# Urukul.net
KiCad netlist of a schematic drawn in Altium Designer
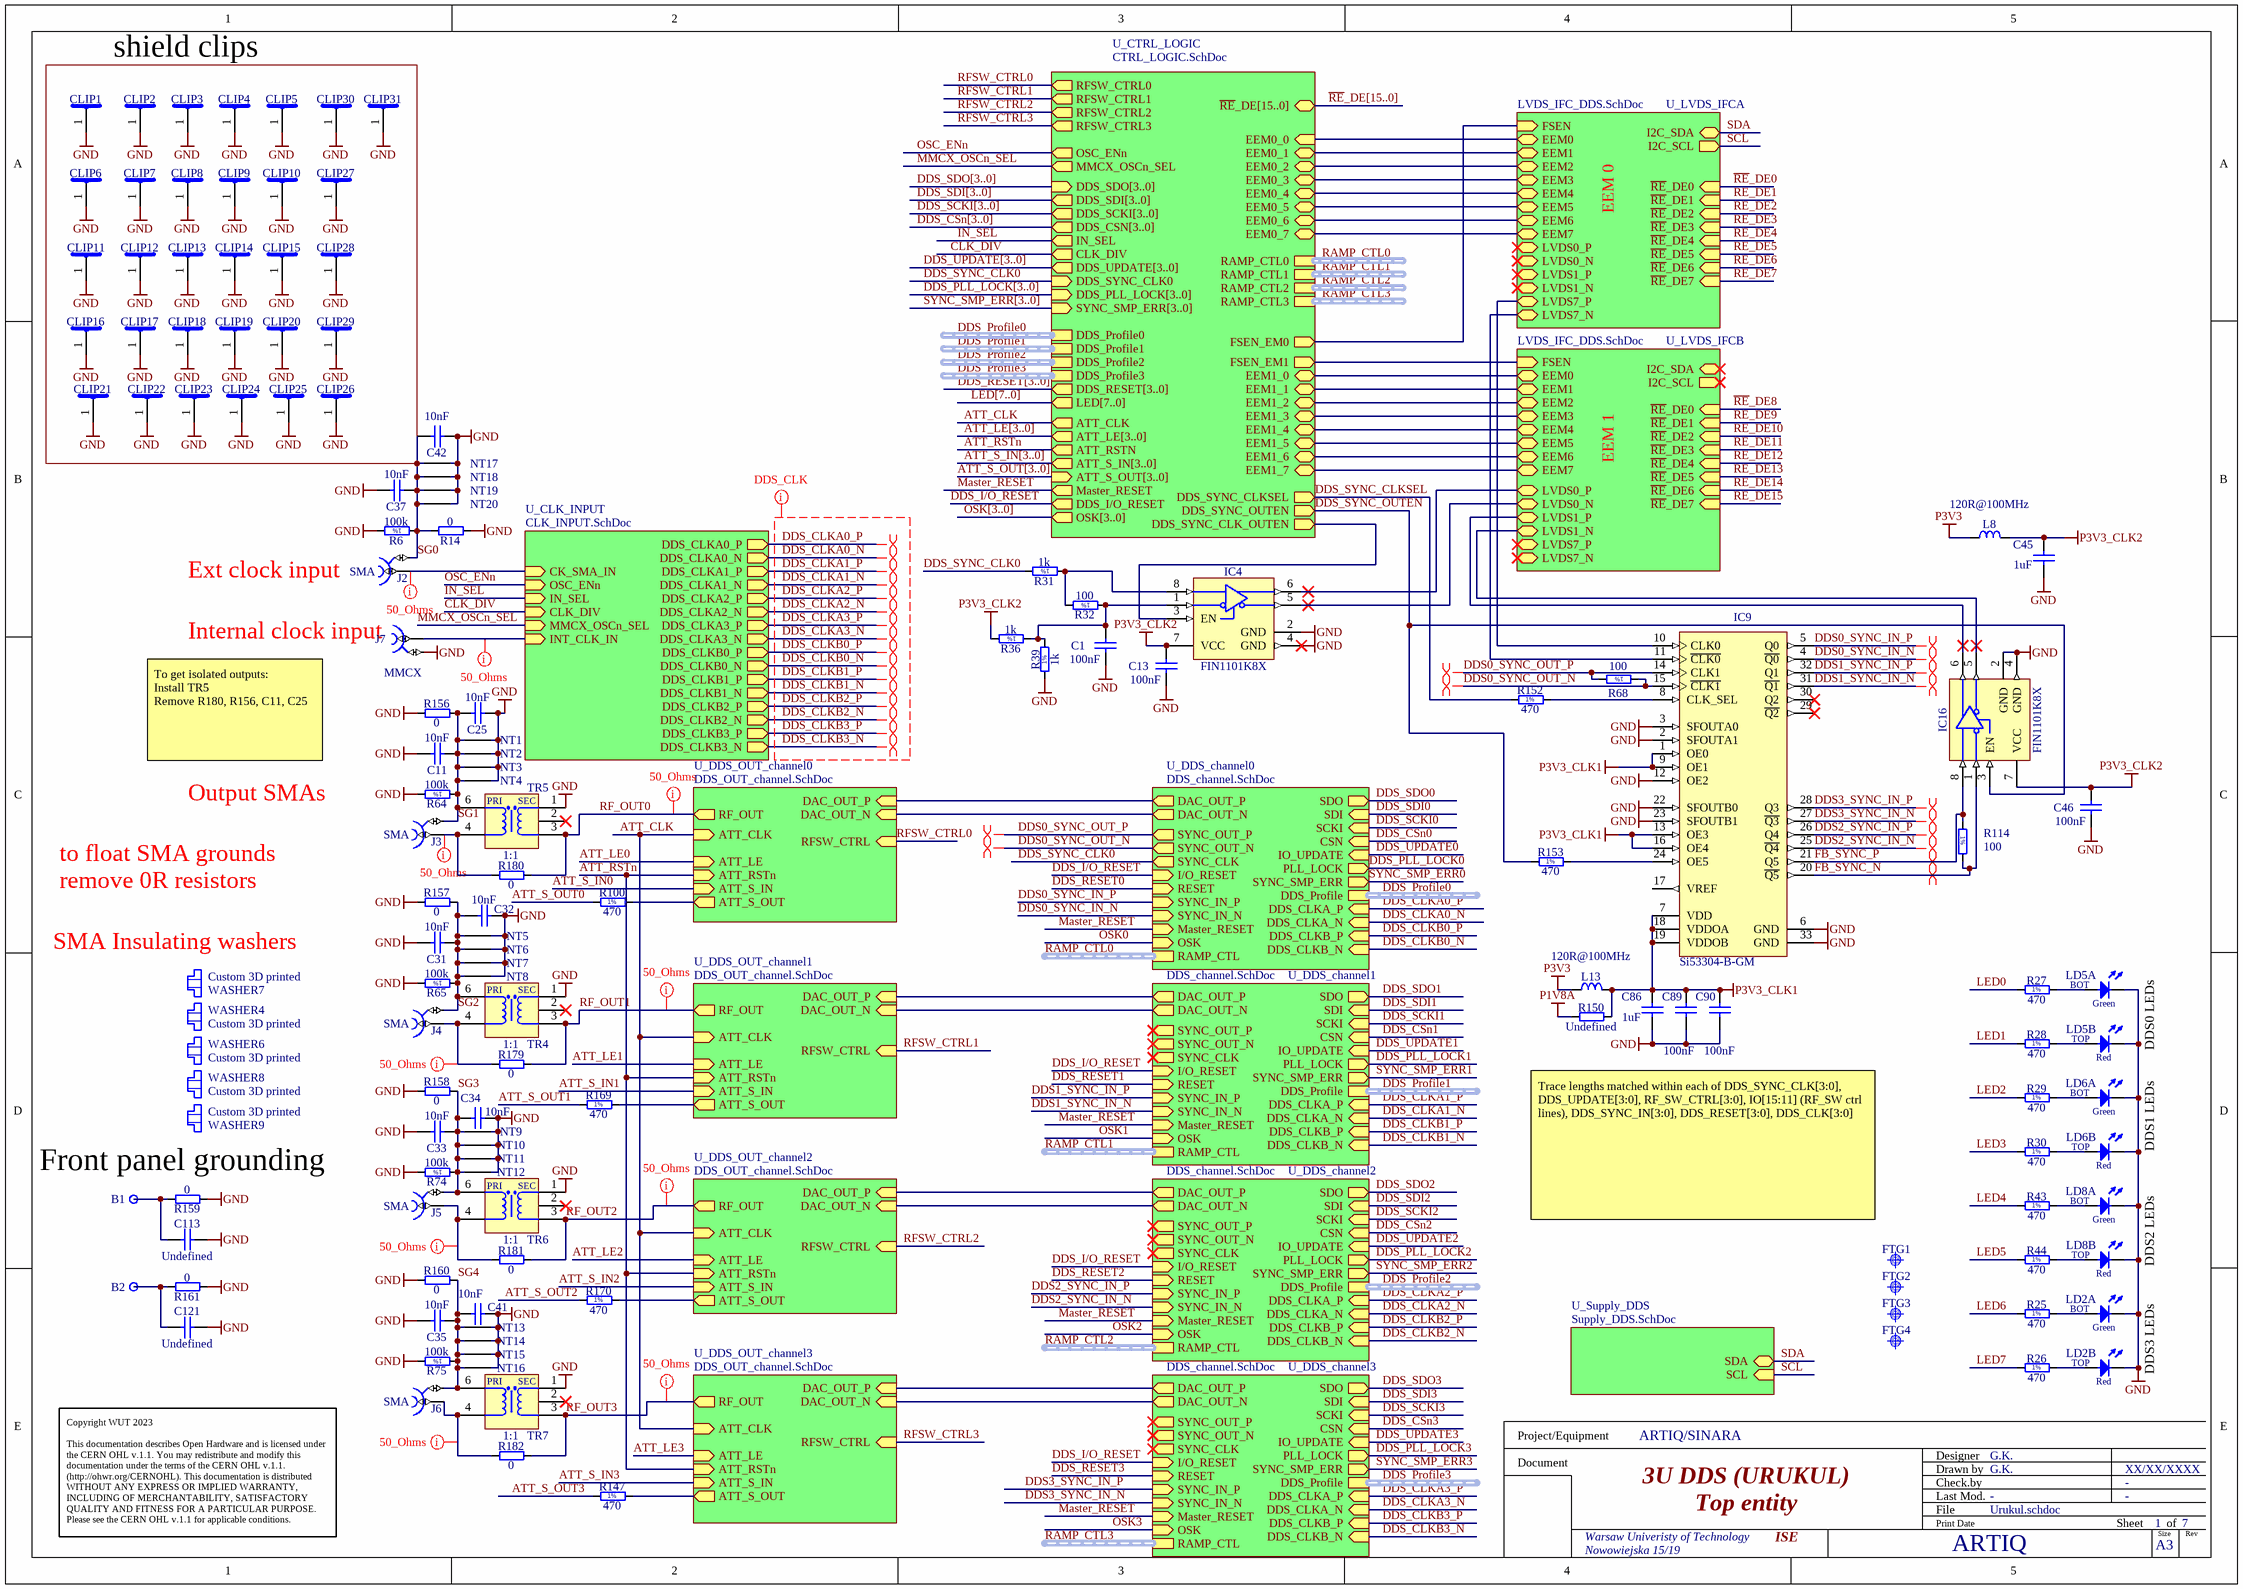
[diagram p0: Urukul.schdoc]

(export (version "E")
  (design (tool "Eeschema 10.0.6"))
  (components
    (comp (ref "B1")
      (value "Plated Hole")
      (footprint "MTG270_500")
      (description "Single Terminal Socket")
      (fields (field (name "PART NUMBER") "PLATED_HOLE2.7_PAD5.0") (field (name "AUTHOR") "CERN DEM JMW"))
      (libsource (lib "Eletro-mechanical") (part "Single Terminal Socket"))
    )
    (comp (ref "B2")
      (value "Plated Hole")
      (footprint "MTG270_500")
      (description "Single Terminal Socket")
      (fields (field (name "PART NUMBER") "PLATED_HOLE2.7_PAD5.0") (field (name "AUTHOR") "CERN DEM JMW"))
      (libsource (lib "Eletro-mechanical") (part "Single Terminal Socket"))
    )
    (comp (ref "C1")
      (value "100nF")
      (footprint "CAPC1005X55N")
      (description "Non-polarised capacitor")
      (fields
        (field (name "PART NUMBER") "CC0402_100NF_16V_10%_X5R")
        (field (name "VOLTAGE") "16V")
        (field (name "AUTHOR") "CERN DEM JLC")
      )
      (libsource (lib "Capacitors") (part "Capacitor - non polarized"))
    )
    (comp (ref "C11")
      (value "10nF")
      (footprint "CAPC1005X55N")
      (description "Non-polarised capacitor")
      (fields
        (field (name "PART NUMBER") "CC0402_10NF_16V_10%_X7R")
        (field (name "VOLTAGE") "16V")
        (field (name "AUTHOR") "CERN DEM JLC")
      )
      (libsource (lib "Capacitors") (part "Capacitor - non polarized"))
    )
    (comp (ref "C13")
      (value "100nF")
      (footprint "CAPC1005X55N")
      (description "Non-polarised capacitor")
      (fields
        (field (name "PART NUMBER") "CC0402_100NF_16V_10%_X5R")
        (field (name "VOLTAGE") "16V")
        (field (name "AUTHOR") "CERN DEM JLC")
      )
      (libsource (lib "Capacitors") (part "Capacitor - non polarized"))
    )
    (comp (ref "C25")
      (value "10nF")
      (footprint "CAPC1005X55N")
      (description "Non-polarised capacitor")
      (fields
        (field (name "PART NUMBER") "CC0402_10NF_16V_10%_X7R")
        (field (name "VOLTAGE") "16V")
        (field (name "AUTHOR") "CERN DEM JLC")
      )
      (libsource (lib "Capacitors") (part "Capacitor - non polarized"))
    )
    (comp (ref "C31")
      (value "10nF")
      (footprint "CAPC1005X55N")
      (description "Non-polarised capacitor")
      (fields
        (field (name "PART NUMBER") "CC0402_10NF_16V_10%_X7R")
        (field (name "VOLTAGE") "16V")
        (field (name "AUTHOR") "CERN DEM JLC")
      )
      (libsource (lib "Capacitors") (part "Capacitor - non polarized"))
    )
    (comp (ref "C32")
      (value "10nF")
      (footprint "CAPC1005X55N")
      (description "Non-polarised capacitor")
      (fields
        (field (name "PART NUMBER") "CC0402_10NF_16V_10%_X7R")
        (field (name "VOLTAGE") "16V")
        (field (name "AUTHOR") "CERN DEM JLC")
      )
      (libsource (lib "Capacitors") (part "Capacitor - non polarized"))
    )
    (comp (ref "C33")
      (value "10nF")
      (footprint "CAPC1005X55N")
      (description "Non-polarised capacitor")
      (fields
        (field (name "PART NUMBER") "CC0402_10NF_16V_10%_X7R")
        (field (name "VOLTAGE") "16V")
        (field (name "AUTHOR") "CERN DEM JLC")
      )
      (libsource (lib "Capacitors") (part "Capacitor - non polarized"))
    )
    (comp (ref "C34")
      (value "10nF")
      (footprint "CAPC1005X55N")
      (description "Non-polarised capacitor")
      (fields
        (field (name "PART NUMBER") "CC0402_10NF_16V_10%_X7R")
        (field (name "VOLTAGE") "16V")
        (field (name "AUTHOR") "CERN DEM JLC")
      )
      (libsource (lib "Capacitors") (part "Capacitor - non polarized"))
    )
    (comp (ref "C35")
      (value "10nF")
      (footprint "CAPC1005X55N")
      (description "Non-polarised capacitor")
      (fields
        (field (name "PART NUMBER") "CC0402_10NF_16V_10%_X7R")
        (field (name "VOLTAGE") "16V")
        (field (name "AUTHOR") "CERN DEM JLC")
      )
      (libsource (lib "Capacitors") (part "Capacitor - non polarized"))
    )
    (comp (ref "C37")
      (value "10nF")
      (footprint "CAPC1005X55N")
      (description "Non-polarised capacitor")
      (fields
        (field (name "PART NUMBER") "CC0402_10NF_16V_10%_X7R")
        (field (name "VOLTAGE") "16V")
        (field (name "AUTHOR") "CERN DEM JLC")
      )
      (libsource (lib "Capacitors") (part "Capacitor - non polarized"))
    )
    (comp (ref "C41")
      (value "10nF")
      (footprint "CAPC1005X55N")
      (description "Non-polarised capacitor")
      (fields
        (field (name "PART NUMBER") "CC0402_10NF_16V_10%_X7R")
        (field (name "VOLTAGE") "16V")
        (field (name "AUTHOR") "CERN DEM JLC")
      )
      (libsource (lib "Capacitors") (part "Capacitor - non polarized"))
    )
    (comp (ref "C42")
      (value "10nF")
      (footprint "CAPC1005X55N")
      (description "Non-polarised capacitor")
      (fields
        (field (name "PART NUMBER") "CC0402_10NF_16V_10%_X7R")
        (field (name "VOLTAGE") "16V")
        (field (name "AUTHOR") "CERN DEM JLC")
      )
      (libsource (lib "Capacitors") (part "Capacitor - non polarized"))
    )
    (comp (ref "C45")
      (value "1uF")
      (footprint "CAPC1005X55N")
      (description "Non-polarised capacitor")
      (fields
        (field (name "PART NUMBER") "CC0402_1UF_16V_10%_X5R")
        (field (name "VOLTAGE") "16V")
        (field (name "AUTHOR") "CERN DEM JLC")
      )
      (libsource (lib "Capacitors") (part "Capacitor - non polarized"))
    )
    (comp (ref "C46")
      (value "100nF")
      (footprint "CAPC1005X55N")
      (description "Non-polarised capacitor")
      (fields
        (field (name "PART NUMBER") "CC0402_100NF_16V_10%_X5R")
        (field (name "VOLTAGE") "16V")
        (field (name "AUTHOR") "CERN DEM JLC")
      )
      (libsource (lib "Capacitors") (part "Capacitor - non polarized"))
    )
    (comp (ref "C86")
      (value "1uF")
      (footprint "CAPC1005X55N")
      (description "Non-polarised capacitor")
      (fields
        (field (name "PART NUMBER") "CC0402_1UF_16V_10%_X5R")
        (field (name "VOLTAGE") "16V")
        (field (name "AUTHOR") "CERN DEM JLC")
      )
      (libsource (lib "Capacitors") (part "Capacitor - non polarized"))
    )
    (comp (ref "C89")
      (value "100nF")
      (footprint "CAPC1005X55N")
      (description "Non-polarised capacitor")
      (fields
        (field (name "PART NUMBER") "CC0402_100NF_16V_10%_X5R")
        (field (name "VOLTAGE") "16V")
        (field (name "AUTHOR") "CERN DEM JLC")
      )
      (libsource (lib "Capacitors") (part "Capacitor - non polarized"))
    )
    (comp (ref "C90")
      (value "100nF")
      (footprint "CAPC1005X55N")
      (description "Non-polarised capacitor")
      (fields
        (field (name "PART NUMBER") "CC0402_100NF_16V_10%_X5R")
        (field (name "VOLTAGE") "16V")
        (field (name "AUTHOR") "CERN DEM JLC")
      )
      (libsource (lib "Capacitors") (part "Capacitor - non polarized"))
    )
    (comp (ref "C113")
      (value "Undefined")
      (footprint "CAPC2012X135N")
      (description "Non-polarised capacitor")
      (fields (field (name "PART NUMBER") "CC0805_NO-VALUE") (field (name "AUTHOR") "CERN DEM JLC"))
      (libsource (lib "Capacitors") (part "Capacitor - non polarized"))
    )
    (comp (ref "C121")
      (value "Undefined")
      (footprint "CAPC2012X135N")
      (description "Non-polarised capacitor")
      (fields (field (name "PART NUMBER") "CC0805_NO-VALUE") (field (name "AUTHOR") "CERN DEM JLC"))
      (libsource (lib "Capacitors") (part "Capacitor - non polarized"))
    )
    (comp (ref "CLIP1")
      (value "S1411-46R")
      (footprint "CLIP_HOLLAND-SHIELDING_LC")
      (description "Surface Mount Clip for PCB Screening Covers")
      (fields (field (name "MANUFACTURER") "HARWIN") (field (name "AUTHOR") "CERN DEM JLC"))
      (libsource (lib "LIBRARY_SCH") (part "SHIELD_CLIP"))
    )
    (comp (ref "CLIP2")
      (value "S1411-46R")
      (footprint "CLIP_HOLLAND-SHIELDING_LC")
      (description "Surface Mount Clip for PCB Screening Covers")
      (fields (field (name "MANUFACTURER") "HARWIN") (field (name "AUTHOR") "CERN DEM JLC"))
      (libsource (lib "LIBRARY_SCH") (part "SHIELD_CLIP"))
    )
    (comp (ref "CLIP3")
      (value "S1411-46R")
      (footprint "CLIP_HOLLAND-SHIELDING_LC")
      (description "Surface Mount Clip for PCB Screening Covers")
      (fields (field (name "MANUFACTURER") "HARWIN") (field (name "AUTHOR") "CERN DEM JLC"))
      (libsource (lib "LIBRARY_SCH") (part "SHIELD_CLIP"))
    )
    (comp (ref "CLIP4")
      (value "S1411-46R")
      (footprint "CLIP_HOLLAND-SHIELDING_LC")
      (description "Surface Mount Clip for PCB Screening Covers")
      (fields (field (name "MANUFACTURER") "HARWIN") (field (name "AUTHOR") "CERN DEM JLC"))
      (libsource (lib "LIBRARY_SCH") (part "SHIELD_CLIP"))
    )
    (comp (ref "CLIP5")
      (value "S1411-46R")
      (footprint "CLIP_HOLLAND-SHIELDING_LC")
      (description "Surface Mount Clip for PCB Screening Covers")
      (fields (field (name "MANUFACTURER") "HARWIN") (field (name "AUTHOR") "CERN DEM JLC"))
      (libsource (lib "LIBRARY_SCH") (part "SHIELD_CLIP"))
    )
    (comp (ref "CLIP6")
      (value "S1411-46R")
      (footprint "CLIP_HOLLAND-SHIELDING_LC")
      (description "Surface Mount Clip for PCB Screening Covers")
      (fields (field (name "MANUFACTURER") "HARWIN") (field (name "AUTHOR") "CERN DEM JLC"))
      (libsource (lib "LIBRARY_SCH") (part "SHIELD_CLIP"))
    )
    (comp (ref "CLIP7")
      (value "S1411-46R")
      (footprint "CLIP_HOLLAND-SHIELDING_LC")
      (description "Surface Mount Clip for PCB Screening Covers")
      (fields (field (name "MANUFACTURER") "HARWIN") (field (name "AUTHOR") "CERN DEM JLC"))
      (libsource (lib "LIBRARY_SCH") (part "SHIELD_CLIP"))
    )
    (comp (ref "CLIP8")
      (value "S1411-46R")
      (footprint "CLIP_HOLLAND-SHIELDING_LC")
      (description "Surface Mount Clip for PCB Screening Covers")
      (fields (field (name "MANUFACTURER") "HARWIN") (field (name "AUTHOR") "CERN DEM JLC"))
      (libsource (lib "LIBRARY_SCH") (part "SHIELD_CLIP"))
    )
    (comp (ref "CLIP9")
      (value "S1411-46R")
      (footprint "CLIP_HOLLAND-SHIELDING_LC")
      (description "Surface Mount Clip for PCB Screening Covers")
      (fields (field (name "MANUFACTURER") "HARWIN") (field (name "AUTHOR") "CERN DEM JLC"))
      (libsource (lib "LIBRARY_SCH") (part "SHIELD_CLIP"))
    )
    (comp (ref "CLIP10")
      (value "S1411-46R")
      (footprint "CLIP_HOLLAND-SHIELDING_LC")
      (description "Surface Mount Clip for PCB Screening Covers")
      (fields (field (name "MANUFACTURER") "HARWIN") (field (name "AUTHOR") "CERN DEM JLC"))
      (libsource (lib "LIBRARY_SCH") (part "SHIELD_CLIP"))
    )
    (comp (ref "CLIP11")
      (value "S1411-46R")
      (footprint "CLIP_HOLLAND-SHIELDING_LC")
      (description "Surface Mount Clip for PCB Screening Covers")
      (fields (field (name "MANUFACTURER") "HARWIN") (field (name "AUTHOR") "CERN DEM JLC"))
      (libsource (lib "LIBRARY_SCH") (part "SHIELD_CLIP"))
    )
    (comp (ref "CLIP12")
      (value "S1411-46R")
      (footprint "CLIP_HOLLAND-SHIELDING_LC")
      (description "Surface Mount Clip for PCB Screening Covers")
      (fields (field (name "MANUFACTURER") "HARWIN") (field (name "AUTHOR") "CERN DEM JLC"))
      (libsource (lib "LIBRARY_SCH") (part "SHIELD_CLIP"))
    )
    (comp (ref "CLIP13")
      (value "S1411-46R")
      (footprint "CLIP_HOLLAND-SHIELDING_LC")
      (description "Surface Mount Clip for PCB Screening Covers")
      (fields (field (name "MANUFACTURER") "HARWIN") (field (name "AUTHOR") "CERN DEM JLC"))
      (libsource (lib "LIBRARY_SCH") (part "SHIELD_CLIP"))
    )
    (comp (ref "CLIP14")
      (value "S1411-46R")
      (footprint "CLIP_HOLLAND-SHIELDING_LC")
      (description "Surface Mount Clip for PCB Screening Covers")
      (fields (field (name "MANUFACTURER") "HARWIN") (field (name "AUTHOR") "CERN DEM JLC"))
      (libsource (lib "LIBRARY_SCH") (part "SHIELD_CLIP"))
    )
    (comp (ref "CLIP15")
      (value "S1411-46R")
      (footprint "CLIP_HOLLAND-SHIELDING_LC")
      (description "Surface Mount Clip for PCB Screening Covers")
      (fields (field (name "MANUFACTURER") "HARWIN") (field (name "AUTHOR") "CERN DEM JLC"))
      (libsource (lib "LIBRARY_SCH") (part "SHIELD_CLIP"))
    )
    (comp (ref "CLIP16")
      (value "S1411-46R")
      (footprint "CLIP_HOLLAND-SHIELDING_LC")
      (description "Surface Mount Clip for PCB Screening Covers")
      (fields (field (name "MANUFACTURER") "HARWIN") (field (name "AUTHOR") "CERN DEM JLC"))
      (libsource (lib "LIBRARY_SCH") (part "SHIELD_CLIP"))
    )
    (comp (ref "CLIP17")
      (value "S1411-46R")
      (footprint "CLIP_HOLLAND-SHIELDING_LC")
      (description "Surface Mount Clip for PCB Screening Covers")
      (fields (field (name "MANUFACTURER") "HARWIN") (field (name "AUTHOR") "CERN DEM JLC"))
      (libsource (lib "LIBRARY_SCH") (part "SHIELD_CLIP"))
    )
    (comp (ref "CLIP18")
      (value "S1411-46R")
      (footprint "CLIP_HOLLAND-SHIELDING_LC")
      (description "Surface Mount Clip for PCB Screening Covers")
      (fields (field (name "MANUFACTURER") "HARWIN") (field (name "AUTHOR") "CERN DEM JLC"))
      (libsource (lib "LIBRARY_SCH") (part "SHIELD_CLIP"))
    )
    (comp (ref "CLIP19")
      (value "S1411-46R")
      (footprint "CLIP_HOLLAND-SHIELDING_LC")
      (description "Surface Mount Clip for PCB Screening Covers")
      (fields (field (name "MANUFACTURER") "HARWIN") (field (name "AUTHOR") "CERN DEM JLC"))
      (libsource (lib "LIBRARY_SCH") (part "SHIELD_CLIP"))
    )
    (comp (ref "CLIP20")
      (value "S1411-46R")
      (footprint "CLIP_HOLLAND-SHIELDING_LC")
      (description "Surface Mount Clip for PCB Screening Covers")
      (fields (field (name "MANUFACTURER") "HARWIN") (field (name "AUTHOR") "CERN DEM JLC"))
      (libsource (lib "LIBRARY_SCH") (part "SHIELD_CLIP"))
    )
    (comp (ref "CLIP21")
      (value "S1411-46R")
      (footprint "CLIP_HOLLAND-SHIELDING_LC")
      (description "Surface Mount Clip for PCB Screening Covers")
      (fields (field (name "MANUFACTURER") "HARWIN") (field (name "AUTHOR") "CERN DEM JLC"))
      (libsource (lib "LIBRARY_SCH") (part "SHIELD_CLIP"))
    )
    (comp (ref "CLIP22")
      (value "S1411-46R")
      (footprint "CLIP_HOLLAND-SHIELDING_LC")
      (description "Surface Mount Clip for PCB Screening Covers")
      (fields (field (name "MANUFACTURER") "HARWIN") (field (name "AUTHOR") "CERN DEM JLC"))
      (libsource (lib "LIBRARY_SCH") (part "SHIELD_CLIP"))
    )
    (comp (ref "CLIP23")
      (value "S1411-46R")
      (footprint "CLIP_HOLLAND-SHIELDING_LC")
      (description "Surface Mount Clip for PCB Screening Covers")
      (fields (field (name "MANUFACTURER") "HARWIN") (field (name "AUTHOR") "CERN DEM JLC"))
      (libsource (lib "LIBRARY_SCH") (part "SHIELD_CLIP"))
    )
    (comp (ref "CLIP24")
      (value "S1411-46R")
      (footprint "CLIP_HOLLAND-SHIELDING_LC")
      (description "Surface Mount Clip for PCB Screening Covers")
      (fields (field (name "MANUFACTURER") "HARWIN") (field (name "AUTHOR") "CERN DEM JLC"))
      (libsource (lib "LIBRARY_SCH") (part "SHIELD_CLIP"))
    )
    (comp (ref "CLIP25")
      (value "S1411-46R")
      (footprint "CLIP_HOLLAND-SHIELDING_LC")
      (description "Surface Mount Clip for PCB Screening Covers")
      (fields (field (name "MANUFACTURER") "HARWIN") (field (name "AUTHOR") "CERN DEM JLC"))
      (libsource (lib "LIBRARY_SCH") (part "SHIELD_CLIP"))
    )
    (comp (ref "CLIP26")
      (value "S1411-46R")
      (footprint "CLIP_HOLLAND-SHIELDING_LC")
      (description "Surface Mount Clip for PCB Screening Covers")
      (fields (field (name "MANUFACTURER") "HARWIN") (field (name "AUTHOR") "CERN DEM JLC"))
      (libsource (lib "LIBRARY_SCH") (part "SHIELD_CLIP"))
    )
    (comp (ref "CLIP27")
      (value "S1411-46R")
      (footprint "CLIP_HOLLAND-SHIELDING_LC")
      (description "Surface Mount Clip for PCB Screening Covers")
      (fields (field (name "MANUFACTURER") "HARWIN") (field (name "AUTHOR") "CERN DEM JLC"))
      (libsource (lib "LIBRARY_SCH") (part "SHIELD_CLIP"))
    )
    (comp (ref "CLIP28")
      (value "S1411-46R")
      (footprint "CLIP_HOLLAND-SHIELDING_LC")
      (description "Surface Mount Clip for PCB Screening Covers")
      (fields (field (name "MANUFACTURER") "HARWIN") (field (name "AUTHOR") "CERN DEM JLC"))
      (libsource (lib "LIBRARY_SCH") (part "SHIELD_CLIP"))
    )
    (comp (ref "CLIP29")
      (value "S1411-46R")
      (footprint "CLIP_HOLLAND-SHIELDING_LC")
      (description "Surface Mount Clip for PCB Screening Covers")
      (fields (field (name "MANUFACTURER") "HARWIN") (field (name "AUTHOR") "CERN DEM JLC"))
      (libsource (lib "LIBRARY_SCH") (part "SHIELD_CLIP"))
    )
    (comp (ref "CLIP30")
      (value "S1411-46R")
      (footprint "CLIP_HOLLAND-SHIELDING_LC")
      (description "Surface Mount Clip for PCB Screening Covers")
      (fields (field (name "MANUFACTURER") "HARWIN") (field (name "AUTHOR") "CERN DEM JLC"))
      (libsource (lib "LIBRARY_SCH") (part "SHIELD_CLIP"))
    )
    (comp (ref "CLIP31")
      (value "S1411-46R")
      (footprint "CLIP_HOLLAND-SHIELDING_LC")
      (description "Surface Mount Clip for PCB Screening Covers")
      (fields (field (name "MANUFACTURER") "HARWIN") (field (name "AUTHOR") "CERN DEM JLC"))
      (libsource (lib "LIBRARY_SCH") (part "SHIELD_CLIP"))
    )
    (comp (ref "FTG1")
      (value "Use only in PCB")
      (footprint "FIDUCIAL_TOP_C100-200")
      (description "Fiducial Target")
      (fields (field (name "PART NUMBER") "FIDUCIAL_TARGET_C100-200") (field (name "AUTHOR") "CERN DEM JLC"))
      (libsource (lib "Eletro-mechanical") (part "Fiducial Target"))
    )
    (comp (ref "FTG2")
      (value "Use only in PCB")
      (footprint "FIDUCIAL_TOP_S100-200")
      (description "Fiducial Target")
      (fields (field (name "PART NUMBER") "FIDUCIAL_TARGET_S100-200") (field (name "AUTHOR") "CERN DEM JLC"))
      (libsource (lib "Eletro-mechanical") (part "Fiducial Target"))
    )
    (comp (ref "FTG3")
      (value "Use only in PCB")
      (footprint "FIDUCIAL_TOP_S200-400")
      (description "Fiducial Target")
      (fields (field (name "PART NUMBER") "FIDUCIAL_TARGET_S200-400") (field (name "AUTHOR") "CERN DEM JLC"))
      (libsource (lib "Eletro-mechanical") (part "Fiducial Target"))
    )
    (comp (ref "FTG4")
      (value "Use only in PCB")
      (footprint "FIDUCIAL_TOP_S100-200")
      (description "Fiducial Target")
      (fields (field (name "PART NUMBER") "FIDUCIAL_TARGET_S100-200") (field (name "AUTHOR") "CERN DEM JLC"))
      (libsource (lib "Eletro-mechanical") (part "Fiducial Target"))
    )
    (comp (ref "IC4")
      (value "FIN1101K8X")
      (footprint "SOP50P310X90-8N")
      (description "LVDS Single Port High Speed Repeater")
      (fields (field (name "MANUFACTURER") "FAIRCHILD SEMICONDUCTOR") (field (name "AUTHOR") "CERN DEM JLC"))
      (libsource (lib "") (part "FIN1101K8X_1"))
    )
    (comp (ref "IC9")
      (value "Si53304-B-GM")
      (footprint "SLAB-QFN-32-2150x2150TP_M")
      (fields (field (name "MANUFACTURER") "Silicon Labs"))
      (libsource (lib "Altium Content Vault") (part "SLAB-Si533X4-QFN-32-33"))
    )
    (comp (ref "IC16")
      (value "FIN1101K8X")
      (footprint "SOP50P310X90-8N")
      (description "LVDS Single Port High Speed Repeater")
      (fields (field (name "MANUFACTURER") "FAIRCHILD SEMICONDUCTOR") (field (name "AUTHOR") "CERN DEM JLC"))
      (libsource (lib "ICs And Semiconductors") (part "FIN1101K8X"))
    )
    (comp (ref "J2")
      (value "SMA")
      (footprint "DELOCK_65848")
      (description "50 Ohm Through Hole SMA Right Angle PCB Jack")
      (fields
        (field (name "PART NUMBER") "DELOCK_65848")
        (field (name "MANUFACTURER") "DELOCK")
        (field (name "AUTHOR") "GK")
      )
      (libsource (lib "Connectors") (part "CON_SMA_DELOCK_65848"))
    )
    (comp (ref "J3")
      (value "SMA")
      (footprint "DELOCK_65848")
      (description "50 Ohm Through Hole SMA Right Angle PCB Jack")
      (fields
        (field (name "PART NUMBER") "DELOCK_65848")
        (field (name "MANUFACTURER") "DELOCK")
        (field (name "AUTHOR") "GK")
      )
      (libsource (lib "Connectors") (part "CON_SMA_DELOCK_65848"))
    )
    (comp (ref "J4")
      (value "SMA")
      (footprint "DELOCK_65848")
      (description "50 Ohm Through Hole SMA Right Angle PCB Jack")
      (fields
        (field (name "PART NUMBER") "DELOCK_65848")
        (field (name "MANUFACTURER") "DELOCK")
        (field (name "AUTHOR") "GK")
      )
      (libsource (lib "Connectors") (part "CON_SMA_DELOCK_65848"))
    )
    (comp (ref "J5")
      (value "SMA")
      (footprint "DELOCK_65848")
      (description "50 Ohm Through Hole SMA Right Angle PCB Jack")
      (fields
        (field (name "PART NUMBER") "DELOCK_65848")
        (field (name "MANUFACTURER") "DELOCK")
        (field (name "AUTHOR") "GK")
      )
      (libsource (lib "Connectors") (part "CON_SMA_DELOCK_65848"))
    )
    (comp (ref "J6")
      (value "SMA")
      (footprint "DELOCK_65848")
      (description "50 Ohm Through Hole SMA Right Angle PCB Jack")
      (fields
        (field (name "PART NUMBER") "DELOCK_65848")
        (field (name "MANUFACTURER") "DELOCK")
        (field (name "AUTHOR") "GK")
      )
      (libsource (lib "Connectors") (part "CON_SMA_DELOCK_65848"))
    )
    (comp (ref "J7")
      (value "MMCX")
      (footprint "SAMTEC_MMCX-J-P-H-ST-TH1")
      (fields
        (field (name "PART NUMBER") "SAMTEC_MMCX-J-P-H-ST-TH1")
        (field (name "MANUFACTURER") "SAMTEC")
        (field (name "MANUFACTURER PART NUMBER") "MMCX-J-P-H-ST-TH1")
        (field (name "AUTHOR") "CERN DEM JLC")
      )
      (libsource (lib "Connectors") (part "Coax_1Female_1Shield"))
    )
    (comp (ref "L8")
      (value "120R@100MHz")
      (footprint "INDC1608X95N")
      (description "Inductor")
      (fields
        (field (name "PART NUMBER") "IND0603_MURATA_BLM18PG121SN1D")
        (field (name "POWER") "2A")
        (field (name "AUTHOR") "CERN DEM BC")
      )
      (libsource (lib "Inductors & Transformers") (part "Inductor"))
    )
    (comp (ref "L13")
      (value "120R@100MHz")
      (footprint "INDC1608X95N")
      (description "Inductor")
      (fields
        (field (name "PART NUMBER") "IND0603_MURATA_BLM18PG121SN1D")
        (field (name "POWER") "2A")
        (field (name "AUTHOR") "CERN DEM BC")
      )
      (libsource (lib "Inductors & Transformers") (part "Inductor"))
    )
    (comp (ref "LD2")
      (value "Red/Green")
      (footprint "LED_DIALIGHT_571-0112F")
      (description "2x LED  Botom Green, Top Red")
      (fields
        (field (name "PART NUMBER") "LED_DIALIGHT_571-0112F")
        (field (name "MANUFACTURER") "DIALIGHT")
        (field (name "AUTHOR") "CERN DEM JLC")
      )
      (libsource (lib "ICs And Semiconductors") (part "LED x2 G-1C2A-BOT_R-3C4A-TOP"))
    )
    (comp (ref "LD5")
      (value "Red/Green")
      (footprint "LED_DIALIGHT_571-0112F")
      (description "2x LED  Botom Green, Top Red")
      (fields
        (field (name "PART NUMBER") "LED_DIALIGHT_571-0112F")
        (field (name "MANUFACTURER") "DIALIGHT")
        (field (name "AUTHOR") "CERN DEM JLC")
      )
      (libsource (lib "ICs And Semiconductors") (part "LED x2 G-1C2A-BOT_R-3C4A-TOP"))
    )
    (comp (ref "LD6")
      (value "Red/Green")
      (footprint "LED_DIALIGHT_571-0112F")
      (description "2x LED  Botom Green, Top Red")
      (fields
        (field (name "PART NUMBER") "LED_DIALIGHT_571-0112F")
        (field (name "MANUFACTURER") "DIALIGHT")
        (field (name "AUTHOR") "CERN DEM JLC")
      )
      (libsource (lib "ICs And Semiconductors") (part "LED x2 G-1C2A-BOT_R-3C4A-TOP"))
    )
    (comp (ref "LD8")
      (value "Red/Green")
      (footprint "LED_DIALIGHT_571-0112F")
      (description "2x LED  Botom Green, Top Red")
      (fields
        (field (name "PART NUMBER") "LED_DIALIGHT_571-0112F")
        (field (name "MANUFACTURER") "DIALIGHT")
        (field (name "AUTHOR") "CERN DEM JLC")
      )
      (libsource (lib "ICs And Semiconductors") (part "LED x2 G-1C2A-BOT_R-3C4A-TOP"))
    )
    (comp (ref "NT1")
      (value "Net Tie")
      (footprint "Net Tie")
      (fields (field (name "AUTHOR") "CERN DEM JLC"))
      (libsource (lib "Eletro-mechanical") (part "Net Tie"))
    )
    (comp (ref "NT2")
      (value "Net Tie")
      (footprint "Net Tie")
      (fields (field (name "AUTHOR") "CERN DEM JLC"))
      (libsource (lib "Eletro-mechanical") (part "Net Tie"))
    )
    (comp (ref "NT3")
      (value "Net Tie")
      (footprint "Net Tie")
      (fields (field (name "AUTHOR") "CERN DEM JLC"))
      (libsource (lib "Eletro-mechanical") (part "Net Tie"))
    )
    (comp (ref "NT4")
      (value "Net Tie")
      (footprint "Net Tie")
      (fields (field (name "AUTHOR") "CERN DEM JLC"))
      (libsource (lib "Eletro-mechanical") (part "Net Tie"))
    )
    (comp (ref "NT5")
      (value "Net Tie")
      (footprint "Net Tie")
      (fields (field (name "AUTHOR") "CERN DEM JLC"))
      (libsource (lib "Eletro-mechanical") (part "Net Tie"))
    )
    (comp (ref "NT6")
      (value "Net Tie")
      (footprint "Net Tie")
      (fields (field (name "AUTHOR") "CERN DEM JLC"))
      (libsource (lib "Eletro-mechanical") (part "Net Tie"))
    )
    (comp (ref "NT7")
      (value "Net Tie")
      (footprint "Net Tie")
      (fields (field (name "AUTHOR") "CERN DEM JLC"))
      (libsource (lib "Eletro-mechanical") (part "Net Tie"))
    )
    (comp (ref "NT8")
      (value "Net Tie")
      (footprint "Net Tie")
      (fields (field (name "AUTHOR") "CERN DEM JLC"))
      (libsource (lib "Eletro-mechanical") (part "Net Tie"))
    )
    (comp (ref "NT9")
      (value "Net Tie")
      (footprint "Net Tie")
      (fields (field (name "AUTHOR") "CERN DEM JLC"))
      (libsource (lib "Eletro-mechanical") (part "Net Tie"))
    )
    (comp (ref "NT10")
      (value "Net Tie")
      (footprint "Net Tie")
      (fields (field (name "AUTHOR") "CERN DEM JLC"))
      (libsource (lib "Eletro-mechanical") (part "Net Tie"))
    )
    (comp (ref "NT11")
      (value "Net Tie")
      (footprint "Net Tie")
      (fields (field (name "AUTHOR") "CERN DEM JLC"))
      (libsource (lib "Eletro-mechanical") (part "Net Tie"))
    )
    (comp (ref "NT12")
      (value "Net Tie")
      (footprint "Net Tie")
      (fields (field (name "AUTHOR") "CERN DEM JLC"))
      (libsource (lib "Eletro-mechanical") (part "Net Tie"))
    )
    (comp (ref "NT13")
      (value "Net Tie")
      (footprint "Net Tie")
      (fields (field (name "AUTHOR") "CERN DEM JLC"))
      (libsource (lib "Eletro-mechanical") (part "Net Tie"))
    )
    (comp (ref "NT14")
      (value "Net Tie")
      (footprint "Net Tie")
      (fields (field (name "AUTHOR") "CERN DEM JLC"))
      (libsource (lib "Eletro-mechanical") (part "Net Tie"))
    )
    (comp (ref "NT15")
      (value "Net Tie")
      (footprint "Net Tie")
      (fields (field (name "AUTHOR") "CERN DEM JLC"))
      (libsource (lib "Eletro-mechanical") (part "Net Tie"))
    )
    (comp (ref "NT16")
      (value "Net Tie")
      (footprint "Net Tie")
      (fields (field (name "AUTHOR") "CERN DEM JLC"))
      (libsource (lib "Eletro-mechanical") (part "Net Tie"))
    )
    (comp (ref "NT17")
      (value "Net Tie")
      (footprint "Net Tie")
      (fields (field (name "AUTHOR") "CERN DEM JLC"))
      (libsource (lib "Eletro-mechanical") (part "Net Tie"))
    )
    (comp (ref "NT18")
      (value "Net Tie")
      (footprint "Net Tie")
      (fields (field (name "AUTHOR") "CERN DEM JLC"))
      (libsource (lib "Eletro-mechanical") (part "Net Tie"))
    )
    (comp (ref "NT19")
      (value "Net Tie")
      (footprint "Net Tie")
      (fields (field (name "AUTHOR") "CERN DEM JLC"))
      (libsource (lib "Eletro-mechanical") (part "Net Tie"))
    )
    (comp (ref "NT20")
      (value "Net Tie")
      (footprint "Net Tie")
      (fields (field (name "AUTHOR") "CERN DEM JLC"))
      (libsource (lib "Eletro-mechanical") (part "Net Tie"))
    )
    (comp (ref "R6")
      (value "100k")
      (footprint "RESC1005X40N")
      (description "Resistor - 1%")
      (fields
        (field (name "PART NUMBER") "R0402_100K_1%_0.0625W_100PPM")
        (field (name "MANUFACTURER") "GENERIC")
        (field (name "AUTHOR") "CERN DEM JLC")
      )
      (libsource (lib "Resistors") (part "Resistor - 1%"))
    )
    (comp (ref "R14")
      (value "0")
      (footprint "RESC1608X55N")
      (description "Resistor")
      (fields
        (field (name "PART NUMBER") "R0603_0R_JUMPER")
        (field (name "MANUFACTURER") "GENERIC")
        (field (name "AUTHOR") "CERN DEM JLC")
      )
      (libsource (lib "Resistors") (part "Resistor"))
    )
    (comp (ref "R25")
      (value "470")
      (footprint "RESC1005X40N")
      (description "Resistor - 1%")
      (fields
        (field (name "PART NUMBER") "R0402_470R_1%_0.0625W_100PPM")
        (field (name "POWER") "0.0625W")
        (field (name "AUTHOR") "CERN DEM JLC")
      )
      (libsource (lib "Resistors") (part "Resistor - 1%"))
    )
    (comp (ref "R26")
      (value "470")
      (footprint "RESC1005X40N")
      (description "Resistor - 1%")
      (fields
        (field (name "PART NUMBER") "R0402_470R_1%_0.0625W_100PPM")
        (field (name "POWER") "0.0625W")
        (field (name "AUTHOR") "CERN DEM JLC")
      )
      (libsource (lib "Resistors") (part "Resistor - 1%"))
    )
    (comp (ref "R27")
      (value "470")
      (footprint "RESC1005X40N")
      (description "Resistor - 1%")
      (fields
        (field (name "PART NUMBER") "R0402_470R_1%_0.0625W_100PPM")
        (field (name "POWER") "0.0625W")
        (field (name "AUTHOR") "CERN DEM JLC")
      )
      (libsource (lib "Resistors") (part "Resistor - 1%"))
    )
    (comp (ref "R28")
      (value "470")
      (footprint "RESC1005X40N")
      (description "Resistor - 1%")
      (fields
        (field (name "PART NUMBER") "R0402_470R_1%_0.0625W_100PPM")
        (field (name "POWER") "0.0625W")
        (field (name "AUTHOR") "CERN DEM JLC")
      )
      (libsource (lib "Resistors") (part "Resistor - 1%"))
    )
    (comp (ref "R29")
      (value "470")
      (footprint "RESC1005X40N")
      (description "Resistor - 1%")
      (fields
        (field (name "PART NUMBER") "R0402_470R_1%_0.0625W_100PPM")
        (field (name "POWER") "0.0625W")
        (field (name "AUTHOR") "CERN DEM JLC")
      )
      (libsource (lib "Resistors") (part "Resistor - 1%"))
    )
    (comp (ref "R30")
      (value "470")
      (footprint "RESC1005X40N")
      (description "Resistor - 1%")
      (fields
        (field (name "PART NUMBER") "R0402_470R_1%_0.0625W_100PPM")
        (field (name "POWER") "0.0625W")
        (field (name "AUTHOR") "CERN DEM JLC")
      )
      (libsource (lib "Resistors") (part "Resistor - 1%"))
    )
    (comp (ref "R31")
      (value "1k")
      (footprint "RESC1005X40N")
      (description "Resistor - 1%")
      (fields
        (field (name "PART NUMBER") "R0402_1K_1%_0.0625W_100PPM")
        (field (name "POWER") "0.0625W")
        (field (name "AUTHOR") "CERN DEM JLC")
      )
      (libsource (lib "Resistors") (part "Resistor - 1%"))
    )
    (comp (ref "R32")
      (value "100")
      (footprint "RESC1005X40N")
      (description "Resistor - 1%")
      (fields
        (field (name "PART NUMBER") "R0402_100R_1%_0.0625W_100PPM")
        (field (name "POWER") "0.0625W")
        (field (name "AUTHOR") "CERN DEM JLC")
      )
      (libsource (lib "Resistors") (part "Resistor - 1%"))
    )
    (comp (ref "R36")
      (value "1k")
      (footprint "RESC1005X40N")
      (description "Resistor - 1%")
      (fields
        (field (name "PART NUMBER") "R0402_1K_1%_0.0625W_100PPM")
        (field (name "POWER") "0.0625W")
        (field (name "AUTHOR") "CERN DEM JLC")
      )
      (libsource (lib "Resistors") (part "Resistor - 1%"))
    )
    (comp (ref "R39")
      (value "1k")
      (footprint "RESC1005X40N")
      (description "Resistor - 1%")
      (fields
        (field (name "PART NUMBER") "R0402_1K_1%_0.0625W_100PPM")
        (field (name "POWER") "0.0625W")
        (field (name "AUTHOR") "CERN DEM JLC")
      )
      (libsource (lib "Resistors") (part "Resistor - 1%"))
    )
    (comp (ref "R43")
      (value "470")
      (footprint "RESC1005X40N")
      (description "Resistor - 1%")
      (fields
        (field (name "PART NUMBER") "R0402_470R_1%_0.0625W_100PPM")
        (field (name "POWER") "0.0625W")
        (field (name "AUTHOR") "CERN DEM JLC")
      )
      (libsource (lib "Resistors") (part "Resistor - 1%"))
    )
    (comp (ref "R44")
      (value "470")
      (footprint "RESC1005X40N")
      (description "Resistor - 1%")
      (fields
        (field (name "PART NUMBER") "R0402_470R_1%_0.0625W_100PPM")
        (field (name "POWER") "0.0625W")
        (field (name "AUTHOR") "CERN DEM JLC")
      )
      (libsource (lib "Resistors") (part "Resistor - 1%"))
    )
    (comp (ref "R64")
      (value "100k")
      (footprint "RESC1005X40N")
      (description "Resistor - 1%")
      (fields
        (field (name "PART NUMBER") "R0402_100K_1%_0.0625W_100PPM")
        (field (name "MANUFACTURER") "GENERIC")
        (field (name "AUTHOR") "CERN DEM JLC")
      )
      (libsource (lib "Resistors") (part "Resistor - 1%"))
    )
    (comp (ref "R65")
      (value "100k")
      (footprint "RESC1005X40N")
      (description "Resistor - 1%")
      (fields
        (field (name "PART NUMBER") "R0402_100K_1%_0.0625W_100PPM")
        (field (name "MANUFACTURER") "GENERIC")
        (field (name "AUTHOR") "CERN DEM JLC")
      )
      (libsource (lib "Resistors") (part "Resistor - 1%"))
    )
    (comp (ref "R68")
      (value "100")
      (footprint "RESC1005X40N")
      (description "Resistor - 1%")
      (fields
        (field (name "PART NUMBER") "R0402_100R_1%_0.0625W_100PPM")
        (field (name "POWER") "0.0625W")
        (field (name "AUTHOR") "CERN DEM JLC")
      )
      (libsource (lib "Resistors") (part "Resistor - 1%"))
    )
    (comp (ref "R74")
      (value "100k")
      (footprint "RESC1005X40N")
      (description "Resistor - 1%")
      (fields
        (field (name "PART NUMBER") "R0402_100K_1%_0.0625W_100PPM")
        (field (name "MANUFACTURER") "GENERIC")
        (field (name "AUTHOR") "CERN DEM JLC")
      )
      (libsource (lib "Resistors") (part "Resistor - 1%"))
    )
    (comp (ref "R75")
      (value "100k")
      (footprint "RESC1005X40N")
      (description "Resistor - 1%")
      (fields
        (field (name "PART NUMBER") "R0402_100K_1%_0.0625W_100PPM")
        (field (name "MANUFACTURER") "GENERIC")
        (field (name "AUTHOR") "CERN DEM JLC")
      )
      (libsource (lib "Resistors") (part "Resistor - 1%"))
    )
    (comp (ref "R100")
      (value "470")
      (footprint "RESC1005X40N")
      (description "Resistor - 1%")
      (fields
        (field (name "PART NUMBER") "R0402_470R_1%_0.0625W_100PPM")
        (field (name "POWER") "0.0625W")
        (field (name "AUTHOR") "CERN DEM JLC")
      )
      (libsource (lib "Resistors") (part "Resistor - 1%"))
    )
    (comp (ref "R114")
      (value "100")
      (footprint "RESC1005X40N")
      (description "Resistor - 1%")
      (fields
        (field (name "PART NUMBER") "R0402_100R_1%_0.0625W_100PPM")
        (field (name "POWER") "0.0625W")
        (field (name "AUTHOR") "CERN DEM JLC")
      )
      (libsource (lib "Resistors") (part "Resistor - 1%"))
    )
    (comp (ref "R147")
      (value "470")
      (footprint "RESC1005X40N")
      (description "Resistor - 1%")
      (fields
        (field (name "PART NUMBER") "R0402_470R_1%_0.0625W_100PPM")
        (field (name "POWER") "0.0625W")
        (field (name "AUTHOR") "CERN DEM JLC")
      )
      (libsource (lib "Resistors") (part "Resistor - 1%"))
    )
    (comp (ref "R150")
      (value "Undefined")
      (footprint "RESC1608X55N")
      (description "Resistor")
      (fields (field (name "PART NUMBER") "R0603_NO-VALUE") (field (name "AUTHOR") "CERN DEM JLC"))
      (libsource (lib "Resistors") (part "Resistor"))
    )
    (comp (ref "R152")
      (value "470")
      (footprint "RESC1005X40N")
      (description "Resistor - 1%")
      (fields
        (field (name "PART NUMBER") "R0402_470R_1%_0.0625W_100PPM")
        (field (name "POWER") "0.0625W")
        (field (name "AUTHOR") "CERN DEM JLC")
      )
      (libsource (lib "Resistors") (part "Resistor - 1%"))
    )
    (comp (ref "R153")
      (value "470")
      (footprint "RESC1005X40N")
      (description "Resistor - 1%")
      (fields
        (field (name "PART NUMBER") "R0402_470R_1%_0.0625W_100PPM")
        (field (name "POWER") "0.0625W")
        (field (name "AUTHOR") "CERN DEM JLC")
      )
      (libsource (lib "Resistors") (part "Resistor - 1%"))
    )
    (comp (ref "R156")
      (value "0")
      (footprint "RESC1608X55N")
      (description "Resistor")
      (fields
        (field (name "PART NUMBER") "R0603_0R_JUMPER")
        (field (name "MANUFACTURER") "GENERIC")
        (field (name "AUTHOR") "CERN DEM JLC")
      )
      (libsource (lib "Resistors") (part "Resistor"))
    )
    (comp (ref "R157")
      (value "0")
      (footprint "RESC1608X55N")
      (description "Resistor")
      (fields
        (field (name "PART NUMBER") "R0603_0R_JUMPER")
        (field (name "MANUFACTURER") "GENERIC")
        (field (name "AUTHOR") "CERN DEM JLC")
      )
      (libsource (lib "Resistors") (part "Resistor"))
    )
    (comp (ref "R158")
      (value "0")
      (footprint "RESC1608X55N")
      (description "Resistor")
      (fields
        (field (name "PART NUMBER") "R0603_0R_JUMPER")
        (field (name "MANUFACTURER") "GENERIC")
        (field (name "AUTHOR") "CERN DEM JLC")
      )
      (libsource (lib "Resistors") (part "Resistor"))
    )
    (comp (ref "R159")
      (value "0")
      (footprint "RESC1608X55N")
      (description "Resistor")
      (fields
        (field (name "PART NUMBER") "R0603_0R_JUMPER")
        (field (name "MANUFACTURER") "GENERIC")
        (field (name "AUTHOR") "CERN DEM JLC")
      )
      (libsource (lib "Resistors") (part "Resistor"))
    )
    (comp (ref "R160")
      (value "0")
      (footprint "RESC1608X55N")
      (description "Resistor")
      (fields
        (field (name "PART NUMBER") "R0603_0R_JUMPER")
        (field (name "MANUFACTURER") "GENERIC")
        (field (name "AUTHOR") "CERN DEM JLC")
      )
      (libsource (lib "Resistors") (part "Resistor"))
    )
    (comp (ref "R161")
      (value "0")
      (footprint "RESC1608X55N")
      (description "Resistor")
      (fields
        (field (name "PART NUMBER") "R0603_0R_JUMPER")
        (field (name "MANUFACTURER") "GENERIC")
        (field (name "AUTHOR") "CERN DEM JLC")
      )
      (libsource (lib "Resistors") (part "Resistor"))
    )
    (comp (ref "R169")
      (value "470")
      (footprint "RESC1005X40N")
      (description "Resistor - 1%")
      (fields
        (field (name "PART NUMBER") "R0402_470R_1%_0.0625W_100PPM")
        (field (name "POWER") "0.0625W")
        (field (name "AUTHOR") "CERN DEM JLC")
      )
      (libsource (lib "Resistors") (part "Resistor - 1%"))
    )
    (comp (ref "R170")
      (value "470")
      (footprint "RESC1005X40N")
      (description "Resistor - 1%")
      (fields
        (field (name "PART NUMBER") "R0402_470R_1%_0.0625W_100PPM")
        (field (name "POWER") "0.0625W")
        (field (name "AUTHOR") "CERN DEM JLC")
      )
      (libsource (lib "Resistors") (part "Resistor - 1%"))
    )
    (comp (ref "R179")
      (value "0")
      (footprint "RESC1005X40N")
      (description "Resistor")
      (fields
        (field (name "PART NUMBER") "R0402_0R_JUMPER")
        (field (name "MANUFACTURER") "GENERIC")
        (field (name "AUTHOR") "CERN DEM JLC")
      )
      (libsource (lib "Resistors") (part "Resistor"))
    )
    (comp (ref "R180")
      (value "0")
      (footprint "RESC1005X40N")
      (description "Resistor")
      (fields
        (field (name "PART NUMBER") "R0402_0R_JUMPER")
        (field (name "MANUFACTURER") "GENERIC")
        (field (name "AUTHOR") "CERN DEM JLC")
      )
      (libsource (lib "Resistors") (part "Resistor"))
    )
    (comp (ref "R181")
      (value "0")
      (footprint "RESC1005X40N")
      (description "Resistor")
      (fields
        (field (name "PART NUMBER") "R0402_0R_JUMPER")
        (field (name "MANUFACTURER") "GENERIC")
        (field (name "AUTHOR") "CERN DEM JLC")
      )
      (libsource (lib "Resistors") (part "Resistor"))
    )
    (comp (ref "R182")
      (value "0")
      (footprint "RESC1005X40N")
      (description "Resistor")
      (fields
        (field (name "PART NUMBER") "R0402_0R_JUMPER")
        (field (name "MANUFACTURER") "GENERIC")
        (field (name "AUTHOR") "CERN DEM JLC")
      )
      (libsource (lib "Resistors") (part "Resistor"))
    )
    (comp (ref "TR4")
      (value "1:1")
      (footprint "XFMR_MINI-CIRCUITS_AT224-1")
      (description "50 Ohm 1.5 To 500MHz RF Transformers")
      (fields
        (field (name "PART NUMBER") "XFMR_MINI-CIRCUITS_TC1-1+")
        (field (name "MANUFACTURER") "MINI-CIRCUITS")
        (field (name "AUTHOR") "CERN DEM JLC")
      )
      (libsource (lib "Inductors & Transformers") (part "XFMR_MINI-CIRCUITS_TC1-1+"))
    )
    (comp (ref "TR5")
      (value "1:1")
      (footprint "XFMR_MINI-CIRCUITS_AT224-1")
      (description "50 Ohm 1.5 To 500MHz RF Transformers")
      (fields
        (field (name "PART NUMBER") "XFMR_MINI-CIRCUITS_TC1-1+")
        (field (name "MANUFACTURER") "MINI-CIRCUITS")
        (field (name "AUTHOR") "CERN DEM JLC")
      )
      (libsource (lib "Inductors & Transformers") (part "XFMR_MINI-CIRCUITS_TC1-1+"))
    )
    (comp (ref "TR6")
      (value "1:1")
      (footprint "XFMR_MINI-CIRCUITS_AT224-1")
      (description "50 Ohm 1.5 To 500MHz RF Transformers")
      (fields
        (field (name "PART NUMBER") "XFMR_MINI-CIRCUITS_TC1-1+")
        (field (name "MANUFACTURER") "MINI-CIRCUITS")
        (field (name "AUTHOR") "CERN DEM JLC")
      )
      (libsource (lib "Inductors & Transformers") (part "XFMR_MINI-CIRCUITS_TC1-1+"))
    )
    (comp (ref "TR7")
      (value "1:1")
      (footprint "XFMR_MINI-CIRCUITS_AT224-1")
      (description "50 Ohm 1.5 To 500MHz RF Transformers")
      (fields
        (field (name "PART NUMBER") "XFMR_MINI-CIRCUITS_TC1-1+")
        (field (name "MANUFACTURER") "MINI-CIRCUITS")
        (field (name "AUTHOR") "CERN DEM JLC")
      )
      (libsource (lib "Inductors & Transformers") (part "XFMR_MINI-CIRCUITS_TC1-1+"))
    )
    (comp (ref "WASHER4")
      (value "Custom 3D printed")
      (footprint "Keystone_7687")
      (description "SMA_Shoulder Washer")
      (fields (field (name "AUTHOR") "GK"))
      (libsource (lib "LIBRARY_SCH") (part "Keystone_7687"))
    )
    (comp (ref "WASHER6")
      (value "Custom 3D printed")
      (footprint "Keystone_7687")
      (description "SMA_Shoulder Washer")
      (fields (field (name "AUTHOR") "GK"))
      (libsource (lib "LIBRARY_SCH") (part "Keystone_7687"))
    )
    (comp (ref "WASHER7")
      (value "Custom 3D printed")
      (footprint "Keystone_7687")
      (description "SMA_Shoulder Washer")
      (fields (field (name "AUTHOR") "GK"))
      (libsource (lib "LIBRARY_SCH") (part "Keystone_7687"))
    )
    (comp (ref "WASHER8")
      (value "Custom 3D printed")
      (footprint "Keystone_7687")
      (description "SMA_Shoulder Washer")
      (fields (field (name "AUTHOR") "GK"))
      (libsource (lib "LIBRARY_SCH") (part "Keystone_7687"))
    )
    (comp (ref "WASHER9")
      (value "Custom 3D printed")
      (footprint "Keystone_7687")
      (description "SMA_Shoulder Washer")
      (fields (field (name "AUTHOR") "GK"))
      (libsource (lib "LIBRARY_SCH") (part "Keystone_7687"))
    )
  )
  (nets
    (net (code "21") (name "/ATT_S_OUT") (class "Default")
      (node (ref "R147") (pin "2") (pinfunction "2_2") (pintype "passive"))
    )
    (net (code "22") (name "/ATT_S_OUT0") (class "Default")
      (node (ref "R100") (pin "1") (pinfunction "1_1") (pintype "passive"))
    )
    (net (code "23") (name "/ATT_S_OUT1") (class "Default")
      (node (ref "R169") (pin "1") (pinfunction "1_1") (pintype "passive"))
    )
    (net (code "24") (name "/ATT_S_OUT2") (class "Default")
      (node (ref "R170") (pin "1") (pinfunction "1_1") (pintype "passive"))
    )
    (net (code "25") (name "/ATT_S_OUT3") (class "Default")
      (node (ref "R147") (pin "1") (pinfunction "1_1") (pintype "passive"))
    )
    (net (code "27") (name "/ATT_S_OUT_1") (class "Default")
      (node (ref "R100") (pin "2") (pinfunction "2_2") (pintype "passive"))
    )
    (net (code "28") (name "/ATT_S_OUT_2") (class "Default")
      (node (ref "R169") (pin "2") (pinfunction "2_2") (pintype "passive"))
    )
    (net (code "29") (name "/ATT_S_OUT_3") (class "Default")
      (node (ref "R170") (pin "2") (pinfunction "2_2") (pintype "passive"))
    )
    (net (code "30") (name "/CK_SMA_IN") (class "Default")
      (node (ref "J2") (pin "1") (pinfunction "1_1") (pintype "bidirectional"))
    )
    (net (code "40") (name "/DDS0_SYNC_IN_N") (class "Default")
      (node (ref "IC9") (pin "4") (pinfunction "~{Q0}_4") (pintype "output"))
    )
    (net (code "41") (name "/DDS0_SYNC_IN_P") (class "Default")
      (node (ref "IC9") (pin "5") (pinfunction "Q0_5") (pintype "output"))
    )
    (net (code "42") (name "/DDS0_SYNC_OUT_N") (class "Default")
      (node (ref "IC9") (pin "15") (pinfunction "~{CLK1}_15") (pintype "input"))
      (node (ref "R68") (pin "1") (pinfunction "1_1") (pintype "passive"))
    )
    (net (code "43") (name "/DDS0_SYNC_OUT_P") (class "Default")
      (node (ref "IC9") (pin "14") (pinfunction "CLK1_14") (pintype "input"))
      (node (ref "R68") (pin "2") (pinfunction "2_2") (pintype "passive"))
    )
    (net (code "44") (name "/DDS1_SYNC_IN_N") (class "Default")
      (node (ref "IC9") (pin "31") (pinfunction "~{Q1}_31") (pintype "output"))
    )
    (net (code "45") (name "/DDS1_SYNC_IN_P") (class "Default")
      (node (ref "IC9") (pin "32") (pinfunction "Q1_32") (pintype "output"))
    )
    (net (code "46") (name "/DDS2_SYNC_IN_N") (class "Default")
      (node (ref "IC9") (pin "25") (pinfunction "~{Q4}_25") (pintype "output"))
    )
    (net (code "47") (name "/DDS2_SYNC_IN_P") (class "Default")
      (node (ref "IC9") (pin "26") (pinfunction "Q4_26") (pintype "output"))
    )
    (net (code "48") (name "/DDS3_SYNC_IN_N") (class "Default")
      (node (ref "IC9") (pin "27") (pinfunction "~{Q3}_27") (pintype "output"))
    )
    (net (code "49") (name "/DDS3_SYNC_IN_P") (class "Default")
      (node (ref "IC9") (pin "28") (pinfunction "Q3_28") (pintype "output"))
    )
    (net (code "97") (name "/DDS_SYNC_CLK0") (class "Default")
      (node (ref "R31") (pin "2") (pinfunction "2_2") (pintype "passive"))
    )
    (net (code "98") (name "/DDS_SYNC_CLKSEL") (class "Default")
      (node (ref "R152") (pin "1") (pinfunction "1_1") (pintype "passive"))
    )
    (net (code "99") (name "/DDS_SYNC_CLK_OUTEN") (class "Default")
      (node (ref "IC4") (pin "3") (pinfunction "EN_3") (pintype "input"))
    )
    (net (code "100") (name "/DDS_SYNC_OUTEN") (class "Default")
      (node (ref "IC16") (pin "3") (pinfunction "EN_3") (pintype "input"))
      (node (ref "R153") (pin "1") (pinfunction "1_1") (pintype "passive"))
    )
    (net (code "122") (name "/FB_SYNC_N") (class "Default")
      (node (ref "IC16") (pin "1") (pinfunction "RIN-_1") (pintype "input"))
      (node (ref "IC9") (pin "20") (pinfunction "~{Q5}_20") (pintype "output"))
      (node (ref "R114") (pin "2") (pinfunction "2_2") (pintype "passive"))
    )
    (net (code "123") (name "/FB_SYNC_P") (class "Default")
      (node (ref "IC16") (pin "8") (pinfunction "RIN+_8") (pintype "input"))
      (node (ref "IC9") (pin "21") (pinfunction "Q5_21") (pintype "output"))
      (node (ref "R114") (pin "1") (pinfunction "1_1") (pintype "passive"))
    )
    (net (code "128") (name "/INT_CLK_IN") (class "Default")
      (node (ref "J7") (pin "1") (pinfunction "1_1") (pintype "bidirectional"))
    )
    (net (code "130") (name "/LED0") (class "Default")
      (node (ref "R27") (pin "1") (pinfunction "1_1") (pintype "passive"))
    )
    (net (code "131") (name "/LED1") (class "Default")
      (node (ref "R28") (pin "1") (pinfunction "1_1") (pintype "passive"))
    )
    (net (code "132") (name "/LED2") (class "Default")
      (node (ref "R29") (pin "1") (pinfunction "1_1") (pintype "passive"))
    )
    (net (code "133") (name "/LED3") (class "Default")
      (node (ref "R30") (pin "1") (pinfunction "1_1") (pintype "passive"))
    )
    (net (code "134") (name "/LED4") (class "Default")
      (node (ref "R43") (pin "1") (pinfunction "1_1") (pintype "passive"))
    )
    (net (code "135") (name "/LED5") (class "Default")
      (node (ref "R44") (pin "1") (pinfunction "1_1") (pintype "passive"))
    )
    (net (code "136") (name "/LED6") (class "Default")
      (node (ref "R25") (pin "1") (pinfunction "1_1") (pintype "passive"))
    )
    (net (code "137") (name "/LED7") (class "Default")
      (node (ref "R26") (pin "1") (pinfunction "1_1") (pintype "passive"))
    )
    (net (code "139") (name "/LVDS0_N") (class "Default")
      (node (ref "IC4") (pin "5") (pinfunction "DOUT-_5") (pintype "output"))
    )
    (net (code "141") (name "/LVDS0_P") (class "Default")
      (node (ref "IC4") (pin "6") (pinfunction "DOUT+_6") (pintype "output"))
    )
    (net (code "144") (name "/LVDS1_N_1") (class "Default")
      (node (ref "IC16") (pin "5") (pinfunction "DOUT-_5") (pintype "output"))
    )
    (net (code "146") (name "/LVDS1_P_1") (class "Default")
      (node (ref "IC16") (pin "6") (pinfunction "DOUT+_6") (pintype "output"))
    )
    (net (code "148") (name "/LVDS7_N_1") (class "Default")
      (node (ref "IC9") (pin "11") (pinfunction "~{CLK0}_11") (pintype "input"))
    )
    (net (code "150") (name "/LVDS7_P_1") (class "Default")
      (node (ref "IC9") (pin "10") (pinfunction "CLK0_10") (pintype "input"))
    )
    (net (code "163") (name "/RF_OUT0") (class "Default")
      (node (ref "R180") (pin "2") (pinfunction "2_2") (pintype "passive"))
      (node (ref "TR5") (pin "3") (pinfunction "S_3") (pintype "passive"))
    )
    (net (code "164") (name "/RF_OUT1") (class "Default")
      (node (ref "R179") (pin "2") (pinfunction "2_2") (pintype "passive"))
      (node (ref "TR4") (pin "3") (pinfunction "S_3") (pintype "passive"))
    )
    (net (code "165") (name "/RF_OUT2") (class "Default")
      (node (ref "R181") (pin "2") (pinfunction "2_2") (pintype "passive"))
      (node (ref "TR6") (pin "3") (pinfunction "S_3") (pintype "passive"))
    )
    (net (code "166") (name "/RF_OUT3") (class "Default")
      (node (ref "R182") (pin "2") (pinfunction "2_2") (pintype "passive"))
      (node (ref "TR7") (pin "3") (pinfunction "S_3") (pintype "passive"))
    )
    (net (code "169") (name "/SG0") (class "Default")
      (node (ref "C37") (pin "1") (pinfunction "1_1") (pintype "passive"))
      (node (ref "C42") (pin "2") (pinfunction "2_2") (pintype "passive"))
      (node (ref "J2") (pin "2") (pinfunction "2_2") (pintype "bidirectional"))
      (node (ref "NT17") (pin "1") (pinfunction "1_1") (pintype "bidirectional"))
      (node (ref "NT18") (pin "1") (pinfunction "1_1") (pintype "bidirectional"))
      (node (ref "NT19") (pin "1") (pinfunction "1_1") (pintype "bidirectional"))
      (node (ref "NT20") (pin "1") (pinfunction "1_1") (pintype "bidirectional"))
      (node (ref "R14") (pin "2") (pinfunction "2_2") (pintype "passive"))
      (node (ref "R6") (pin "2") (pinfunction "2_2") (pintype "passive"))
    )
    (net (code "170") (name "/SG1") (class "Default")
      (node (ref "C11") (pin "1") (pinfunction "1_1") (pintype "passive"))
      (node (ref "C25") (pin "2") (pinfunction "2_2") (pintype "passive"))
      (node (ref "J3") (pin "2") (pinfunction "2_2") (pintype "bidirectional"))
      (node (ref "NT1") (pin "1") (pinfunction "1_1") (pintype "bidirectional"))
      (node (ref "NT2") (pin "1") (pinfunction "1_1") (pintype "bidirectional"))
      (node (ref "NT3") (pin "1") (pinfunction "1_1") (pintype "bidirectional"))
      (node (ref "NT4") (pin "1") (pinfunction "1_1") (pintype "bidirectional"))
      (node (ref "R156") (pin "2") (pinfunction "2_2") (pintype "passive"))
      (node (ref "R64") (pin "2") (pinfunction "2_2") (pintype "passive"))
      (node (ref "TR5") (pin "6") (pinfunction "PDOT_6") (pintype "passive"))
    )
    (net (code "171") (name "/SG2") (class "Default")
      (node (ref "C31") (pin "1") (pinfunction "1_1") (pintype "passive"))
      (node (ref "C32") (pin "2") (pinfunction "2_2") (pintype "passive"))
      (node (ref "J4") (pin "2") (pinfunction "2_2") (pintype "bidirectional"))
      (node (ref "NT5") (pin "1") (pinfunction "1_1") (pintype "bidirectional"))
      (node (ref "NT6") (pin "1") (pinfunction "1_1") (pintype "bidirectional"))
      (node (ref "NT7") (pin "1") (pinfunction "1_1") (pintype "bidirectional"))
      (node (ref "NT8") (pin "1") (pinfunction "1_1") (pintype "bidirectional"))
      (node (ref "R157") (pin "2") (pinfunction "2_2") (pintype "passive"))
      (node (ref "R65") (pin "2") (pinfunction "2_2") (pintype "passive"))
      (node (ref "TR4") (pin "6") (pinfunction "PDOT_6") (pintype "passive"))
    )
    (net (code "172") (name "/SG3") (class "Default")
      (node (ref "C33") (pin "1") (pinfunction "1_1") (pintype "passive"))
      (node (ref "C34") (pin "2") (pinfunction "2_2") (pintype "passive"))
      (node (ref "J5") (pin "2") (pinfunction "2_2") (pintype "bidirectional"))
      (node (ref "NT10") (pin "1") (pinfunction "1_1") (pintype "bidirectional"))
      (node (ref "NT11") (pin "1") (pinfunction "1_1") (pintype "bidirectional"))
      (node (ref "NT12") (pin "1") (pinfunction "1_1") (pintype "bidirectional"))
      (node (ref "NT9") (pin "1") (pinfunction "1_1") (pintype "bidirectional"))
      (node (ref "R158") (pin "2") (pinfunction "2_2") (pintype "passive"))
      (node (ref "R74") (pin "2") (pinfunction "2_2") (pintype "passive"))
      (node (ref "TR6") (pin "6") (pinfunction "PDOT_6") (pintype "passive"))
    )
    (net (code "173") (name "/SG4") (class "Default")
      (node (ref "C35") (pin "1") (pinfunction "1_1") (pintype "passive"))
      (node (ref "C41") (pin "2") (pinfunction "2_2") (pintype "passive"))
      (node (ref "J6") (pin "2") (pinfunction "2_2") (pintype "bidirectional"))
      (node (ref "NT13") (pin "1") (pinfunction "1_1") (pintype "bidirectional"))
      (node (ref "NT14") (pin "1") (pinfunction "1_1") (pintype "bidirectional"))
      (node (ref "NT15") (pin "1") (pinfunction "1_1") (pintype "bidirectional"))
      (node (ref "NT16") (pin "1") (pinfunction "1_1") (pintype "bidirectional"))
      (node (ref "R160") (pin "2") (pinfunction "2_2") (pintype "passive"))
      (node (ref "R75") (pin "2") (pinfunction "2_2") (pintype "passive"))
      (node (ref "TR7") (pin "6") (pinfunction "PDOT_6") (pintype "passive"))
    )
    (net (code "213") (name "GND") (class "Default")
      (node (ref "C1") (pin "1") (pinfunction "1_1") (pintype "passive"))
      (node (ref "C11") (pin "2") (pinfunction "2_2") (pintype "passive"))
      (node (ref "C113") (pin "2") (pinfunction "2_2") (pintype "passive"))
      (node (ref "C121") (pin "2") (pinfunction "2_2") (pintype "passive"))
      (node (ref "C13") (pin "1") (pinfunction "1_1") (pintype "passive"))
      (node (ref "C25") (pin "1") (pinfunction "1_1") (pintype "passive"))
      (node (ref "C31") (pin "2") (pinfunction "2_2") (pintype "passive"))
      (node (ref "C32") (pin "1") (pinfunction "1_1") (pintype "passive"))
      (node (ref "C33") (pin "2") (pinfunction "2_2") (pintype "passive"))
      (node (ref "C34") (pin "1") (pinfunction "1_1") (pintype "passive"))
      (node (ref "C35") (pin "2") (pinfunction "2_2") (pintype "passive"))
      (node (ref "C37") (pin "2") (pinfunction "2_2") (pintype "passive"))
      (node (ref "C41") (pin "1") (pinfunction "1_1") (pintype "passive"))
      (node (ref "C42") (pin "1") (pinfunction "1_1") (pintype "passive"))
      (node (ref "C45") (pin "1") (pinfunction "1_1") (pintype "passive"))
      (node (ref "C46") (pin "1") (pinfunction "1_1") (pintype "passive"))
      (node (ref "C86") (pin "1") (pinfunction "1_1") (pintype "passive"))
      (node (ref "C89") (pin "1") (pinfunction "1_1") (pintype "passive"))
      (node (ref "C90") (pin "1") (pinfunction "1_1") (pintype "passive"))
      (node (ref "CLIP1") (pin "1") (pinfunction "1_1") (pintype "passive"))
      (node (ref "CLIP10") (pin "1") (pinfunction "1_1") (pintype "passive"))
      (node (ref "CLIP11") (pin "1") (pinfunction "1_1") (pintype "passive"))
      (node (ref "CLIP12") (pin "1") (pinfunction "1_1") (pintype "passive"))
      (node (ref "CLIP13") (pin "1") (pinfunction "1_1") (pintype "passive"))
      (node (ref "CLIP14") (pin "1") (pinfunction "1_1") (pintype "passive"))
      (node (ref "CLIP15") (pin "1") (pinfunction "1_1") (pintype "passive"))
      (node (ref "CLIP16") (pin "1") (pinfunction "1_1") (pintype "passive"))
      (node (ref "CLIP17") (pin "1") (pinfunction "1_1") (pintype "passive"))
      (node (ref "CLIP18") (pin "1") (pinfunction "1_1") (pintype "passive"))
      (node (ref "CLIP19") (pin "1") (pinfunction "1_1") (pintype "passive"))
      (node (ref "CLIP2") (pin "1") (pinfunction "1_1") (pintype "passive"))
      (node (ref "CLIP20") (pin "1") (pinfunction "1_1") (pintype "passive"))
      (node (ref "CLIP21") (pin "1") (pinfunction "1_1") (pintype "passive"))
      (node (ref "CLIP22") (pin "1") (pinfunction "1_1") (pintype "passive"))
      (node (ref "CLIP23") (pin "1") (pinfunction "1_1") (pintype "passive"))
      (node (ref "CLIP24") (pin "1") (pinfunction "1_1") (pintype "passive"))
      (node (ref "CLIP25") (pin "1") (pinfunction "1_1") (pintype "passive"))
      (node (ref "CLIP26") (pin "1") (pinfunction "1_1") (pintype "passive"))
      (node (ref "CLIP27") (pin "1") (pinfunction "1_1") (pintype "passive"))
      (node (ref "CLIP28") (pin "1") (pinfunction "1_1") (pintype "passive"))
      (node (ref "CLIP29") (pin "1") (pinfunction "1_1") (pintype "passive"))
      (node (ref "CLIP3") (pin "1") (pinfunction "1_1") (pintype "passive"))
      (node (ref "CLIP30") (pin "1") (pinfunction "1_1") (pintype "passive"))
      (node (ref "CLIP31") (pin "1") (pinfunction "1_1") (pintype "passive"))
      (node (ref "CLIP4") (pin "1") (pinfunction "1_1") (pintype "passive"))
      (node (ref "CLIP5") (pin "1") (pinfunction "1_1") (pintype "passive"))
      (node (ref "CLIP6") (pin "1") (pinfunction "1_1") (pintype "passive"))
      (node (ref "CLIP7") (pin "1") (pinfunction "1_1") (pintype "passive"))
      (node (ref "CLIP8") (pin "1") (pinfunction "1_1") (pintype "passive"))
      (node (ref "CLIP9") (pin "1") (pinfunction "1_1") (pintype "passive"))
      (node (ref "IC16") (pin "2") (pinfunction "GND_2") (pintype "power_in"))
      (node (ref "IC16") (pin "4") (pinfunction "GND_4") (pintype "output"))
      (node (ref "IC4") (pin "2") (pinfunction "GND_2") (pintype "power_in"))
      (node (ref "IC4") (pin "4") (pinfunction "GND_4") (pintype "output"))
      (node (ref "IC9") (pin "12") (pinfunction "OE2_12") (pintype "input"))
      (node (ref "IC9") (pin "2") (pinfunction "SFOUTA1_2") (pintype "input"))
      (node (ref "IC9") (pin "22") (pinfunction "SFOUTB0_22") (pintype "input"))
      (node (ref "IC9") (pin "23") (pinfunction "SFOUTB1_23") (pintype "input"))
      (node (ref "IC9") (pin "3") (pinfunction "SFOUTA0_3") (pintype "input"))
      (node (ref "IC9") (pin "33") (pinfunction "GND_33") (pintype "power_in"))
      (node (ref "IC9") (pin "6") (pinfunction "GND_6") (pintype "power_in"))
      (node (ref "J7") (pin "2") (pinfunction "2_2") (pintype "bidirectional"))
      (node (ref "LD2") (pin "1") (pinfunction "C_1") (pintype "passive"))
      (node (ref "LD2") (pin "3") (pinfunction "C_3") (pintype "passive"))
      (node (ref "LD5") (pin "1") (pinfunction "C_1") (pintype "passive"))
      (node (ref "LD5") (pin "3") (pinfunction "C_3") (pintype "passive"))
      (node (ref "LD6") (pin "1") (pinfunction "C_1") (pintype "passive"))
      (node (ref "LD6") (pin "3") (pinfunction "C_3") (pintype "passive"))
      (node (ref "LD8") (pin "1") (pinfunction "C_1") (pintype "passive"))
      (node (ref "LD8") (pin "3") (pinfunction "C_3") (pintype "passive"))
      (node (ref "NT1") (pin "2") (pinfunction "2_2") (pintype "bidirectional"))
      (node (ref "NT10") (pin "2") (pinfunction "2_2") (pintype "bidirectional"))
      (node (ref "NT11") (pin "2") (pinfunction "2_2") (pintype "bidirectional"))
      (node (ref "NT12") (pin "2") (pinfunction "2_2") (pintype "bidirectional"))
      (node (ref "NT13") (pin "2") (pinfunction "2_2") (pintype "bidirectional"))
      (node (ref "NT14") (pin "2") (pinfunction "2_2") (pintype "bidirectional"))
      (node (ref "NT15") (pin "2") (pinfunction "2_2") (pintype "bidirectional"))
      (node (ref "NT16") (pin "2") (pinfunction "2_2") (pintype "bidirectional"))
      (node (ref "NT17") (pin "2") (pinfunction "2_2") (pintype "bidirectional"))
      (node (ref "NT18") (pin "2") (pinfunction "2_2") (pintype "bidirectional"))
      (node (ref "NT19") (pin "2") (pinfunction "2_2") (pintype "bidirectional"))
      (node (ref "NT2") (pin "2") (pinfunction "2_2") (pintype "bidirectional"))
      (node (ref "NT20") (pin "2") (pinfunction "2_2") (pintype "bidirectional"))
      (node (ref "NT3") (pin "2") (pinfunction "2_2") (pintype "bidirectional"))
      (node (ref "NT4") (pin "2") (pinfunction "2_2") (pintype "bidirectional"))
      (node (ref "NT5") (pin "2") (pinfunction "2_2") (pintype "bidirectional"))
      (node (ref "NT6") (pin "2") (pinfunction "2_2") (pintype "bidirectional"))
      (node (ref "NT7") (pin "2") (pinfunction "2_2") (pintype "bidirectional"))
      (node (ref "NT8") (pin "2") (pinfunction "2_2") (pintype "bidirectional"))
      (node (ref "NT9") (pin "2") (pinfunction "2_2") (pintype "bidirectional"))
      (node (ref "R14") (pin "1") (pinfunction "1_1") (pintype "passive"))
      (node (ref "R156") (pin "1") (pinfunction "1_1") (pintype "passive"))
      (node (ref "R157") (pin "1") (pinfunction "1_1") (pintype "passive"))
      (node (ref "R158") (pin "1") (pinfunction "1_1") (pintype "passive"))
      (node (ref "R159") (pin "1") (pinfunction "1_1") (pintype "passive"))
      (node (ref "R160") (pin "1") (pinfunction "1_1") (pintype "passive"))
      (node (ref "R161") (pin "1") (pinfunction "1_1") (pintype "passive"))
      (node (ref "R39") (pin "1") (pinfunction "1_1") (pintype "passive"))
      (node (ref "R6") (pin "1") (pinfunction "1_1") (pintype "passive"))
      (node (ref "R64") (pin "1") (pinfunction "1_1") (pintype "passive"))
      (node (ref "R65") (pin "1") (pinfunction "1_1") (pintype "passive"))
      (node (ref "R74") (pin "1") (pinfunction "1_1") (pintype "passive"))
      (node (ref "R75") (pin "1") (pinfunction "1_1") (pintype "passive"))
      (node (ref "TR4") (pin "1") (pinfunction "SDOT_1") (pintype "passive"))
      (node (ref "TR5") (pin "1") (pinfunction "SDOT_1") (pintype "passive"))
      (node (ref "TR6") (pin "1") (pinfunction "SDOT_1") (pintype "passive"))
      (node (ref "TR7") (pin "1") (pinfunction "SDOT_1") (pintype "passive"))
    )
    (net (code "214") (name "Net-(B1-Pad1)") (class "Default")
      (node (ref "B1") (pin "1") (pinfunction "1_1") (pintype "bidirectional"))
      (node (ref "C113") (pin "1") (pinfunction "1_1") (pintype "passive"))
      (node (ref "R159") (pin "2") (pinfunction "2_2") (pintype "passive"))
    )
    (net (code "215") (name "Net-(B2-Pad1)") (class "Default")
      (node (ref "B2") (pin "1") (pinfunction "1_1") (pintype "bidirectional"))
      (node (ref "C121") (pin "1") (pinfunction "1_1") (pintype "passive"))
      (node (ref "R161") (pin "2") (pinfunction "2_2") (pintype "passive"))
    )
    (net (code "216") (name "Net-(IC4-RIN+)") (class "Default")
      (node (ref "IC4") (pin "8") (pinfunction "RIN+_8") (pintype "input"))
      (node (ref "R31") (pin "1") (pinfunction "1_1") (pintype "passive"))
      (node (ref "R32") (pin "2") (pinfunction "2_2") (pintype "passive"))
    )
    (net (code "217") (name "Net-(IC4-RIN-)") (class "Default")
      (node (ref "C1") (pin "2") (pinfunction "2_2") (pintype "passive"))
      (node (ref "IC4") (pin "1") (pinfunction "RIN-_1") (pintype "input"))
      (node (ref "R32") (pin "1") (pinfunction "1_1") (pintype "passive"))
      (node (ref "R36") (pin "1") (pinfunction "1_1") (pintype "passive"))
      (node (ref "R39") (pin "2") (pinfunction "2_2") (pintype "passive"))
    )
    (net (code "218") (name "Net-(IC9-CLK_SEL)") (class "Default")
      (node (ref "IC9") (pin "8") (pinfunction "CLK_SEL_8") (pintype "input"))
      (node (ref "R152") (pin "2") (pinfunction "2_2") (pintype "passive"))
    )
    (net (code "219") (name "Net-(IC9-OE5)") (class "Default")
      (node (ref "IC9") (pin "24") (pinfunction "OE5_24") (pintype "input"))
      (node (ref "R153") (pin "2") (pinfunction "2_2") (pintype "passive"))
    )
    (net (code "220") (name "Net-(LD2A-A)") (class "Default")
      (node (ref "LD2") (pin "2") (pinfunction "A_2") (pintype "passive"))
      (node (ref "R25") (pin "2") (pinfunction "2_2") (pintype "passive"))
    )
    (net (code "221") (name "Net-(LD2B-A)") (class "Default")
      (node (ref "LD2") (pin "4") (pinfunction "A_4") (pintype "passive"))
      (node (ref "R26") (pin "2") (pinfunction "2_2") (pintype "passive"))
    )
    (net (code "222") (name "Net-(LD5A-A)") (class "Default")
      (node (ref "LD5") (pin "2") (pinfunction "A_2") (pintype "passive"))
      (node (ref "R27") (pin "2") (pinfunction "2_2") (pintype "passive"))
    )
    (net (code "223") (name "Net-(LD5B-A)") (class "Default")
      (node (ref "LD5") (pin "4") (pinfunction "A_4") (pintype "passive"))
      (node (ref "R28") (pin "2") (pinfunction "2_2") (pintype "passive"))
    )
    (net (code "224") (name "Net-(LD6A-A)") (class "Default")
      (node (ref "LD6") (pin "2") (pinfunction "A_2") (pintype "passive"))
      (node (ref "R29") (pin "2") (pinfunction "2_2") (pintype "passive"))
    )
    (net (code "225") (name "Net-(LD6B-A)") (class "Default")
      (node (ref "LD6") (pin "4") (pinfunction "A_4") (pintype "passive"))
      (node (ref "R30") (pin "2") (pinfunction "2_2") (pintype "passive"))
    )
    (net (code "226") (name "Net-(LD8A-A)") (class "Default")
      (node (ref "LD8") (pin "2") (pinfunction "A_2") (pintype "passive"))
      (node (ref "R43") (pin "2") (pinfunction "2_2") (pintype "passive"))
    )
    (net (code "227") (name "Net-(LD8B-A)") (class "Default")
      (node (ref "LD8") (pin "4") (pinfunction "A_4") (pintype "passive"))
      (node (ref "R44") (pin "2") (pinfunction "2_2") (pintype "passive"))
    )
    (net (code "228") (name "Net-(TR4-P)") (class "Default")
      (node (ref "J4") (pin "1") (pinfunction "1_1") (pintype "bidirectional"))
      (node (ref "R179") (pin "1") (pinfunction "1_1") (pintype "passive"))
      (node (ref "TR4") (pin "4") (pinfunction "P_4") (pintype "passive"))
    )
    (net (code "229") (name "Net-(TR5-P)") (class "Default")
      (node (ref "J3") (pin "1") (pinfunction "1_1") (pintype "bidirectional"))
      (node (ref "R180") (pin "1") (pinfunction "1_1") (pintype "passive"))
      (node (ref "TR5") (pin "4") (pinfunction "P_4") (pintype "passive"))
    )
    (net (code "230") (name "Net-(TR6-P)") (class "Default")
      (node (ref "J5") (pin "1") (pinfunction "1_1") (pintype "bidirectional"))
      (node (ref "R181") (pin "1") (pinfunction "1_1") (pintype "passive"))
      (node (ref "TR6") (pin "4") (pinfunction "P_4") (pintype "passive"))
    )
    (net (code "231") (name "Net-(TR7-P)") (class "Default")
      (node (ref "J6") (pin "1") (pinfunction "1_1") (pintype "bidirectional"))
      (node (ref "R182") (pin "1") (pinfunction "1_1") (pintype "passive"))
      (node (ref "TR7") (pin "4") (pinfunction "P_4") (pintype "passive"))
    )
    (net (code "232") (name "P1V8A") (class "Default")
      (node (ref "R150") (pin "1") (pinfunction "1_1") (pintype "passive"))
    )
    (net (code "233") (name "P3V3") (class "Default")
      (node (ref "L13") (pin "2") (pinfunction "2_2") (pintype "passive"))
      (node (ref "L8") (pin "2") (pinfunction "2_2") (pintype "passive"))
    )
    (net (code "234") (name "P3V3_CLK1") (class "Default")
      (node (ref "C86") (pin "2") (pinfunction "2_2") (pintype "passive"))
      (node (ref "C89") (pin "2") (pinfunction "2_2") (pintype "passive"))
      (node (ref "C90") (pin "2") (pinfunction "2_2") (pintype "passive"))
      (node (ref "IC9") (pin "1") (pinfunction "OE0_1") (pintype "input"))
      (node (ref "IC9") (pin "13") (pinfunction "OE3_13") (pintype "input"))
      (node (ref "IC9") (pin "16") (pinfunction "OE4_16") (pintype "input"))
      (node (ref "IC9") (pin "18") (pinfunction "VDDOA_18") (pintype "power_in"))
      (node (ref "IC9") (pin "19") (pinfunction "VDDOB_19") (pintype "power_in"))
      (node (ref "IC9") (pin "7") (pinfunction "VDD_7") (pintype "power_in"))
      (node (ref "IC9") (pin "9") (pinfunction "OE1_9") (pintype "input"))
      (node (ref "L13") (pin "1") (pinfunction "1_1") (pintype "passive"))
      (node (ref "R150") (pin "2") (pinfunction "2_2") (pintype "passive"))
    )
    (net (code "235") (name "P3V3_CLK2") (class "Default")
      (node (ref "C13") (pin "2") (pinfunction "2_2") (pintype "passive"))
      (node (ref "C45") (pin "2") (pinfunction "2_2") (pintype "passive"))
      (node (ref "C46") (pin "2") (pinfunction "2_2") (pintype "passive"))
      (node (ref "IC16") (pin "7") (pinfunction "VCC_7") (pintype "power_in"))
      (node (ref "IC4") (pin "7") (pinfunction "VCC_7") (pintype "power_in"))
      (node (ref "L8") (pin "1") (pinfunction "1_1") (pintype "passive"))
      (node (ref "R36") (pin "2") (pinfunction "2_2") (pintype "passive"))
    )
    (net (code "236") (name "unconnected-(IC9-Q2-Pad30)") (class "Default")
      (node (ref "IC9") (pin "30") (pinfunction "Q2_30") (pintype "output+no_connect"))
    )
    (net (code "237") (name "unconnected-(IC9-VREF-Pad17)") (class "Default")
      (node (ref "IC9") (pin "17") (pinfunction "VREF_17") (pintype "output"))
    )
    (net (code "238") (name "unconnected-(IC9-~{Q2}-Pad29)") (class "Default")
      (node (ref "IC9") (pin "29") (pinfunction "~{Q2}_29") (pintype "output+no_connect"))
    )
    (net (code "239") (name "unconnected-(TR4-NU-Pad2)") (class "Default")
      (node (ref "TR4") (pin "2") (pinfunction "NU_2") (pintype "passive+no_connect"))
    )
    (net (code "240") (name "unconnected-(TR5-NU-Pad2)") (class "Default")
      (node (ref "TR5") (pin "2") (pinfunction "NU_2") (pintype "passive+no_connect"))
    )
    (net (code "241") (name "unconnected-(TR6-NU-Pad2)") (class "Default")
      (node (ref "TR6") (pin "2") (pinfunction "NU_2") (pintype "passive+no_connect"))
    )
    (net (code "242") (name "unconnected-(TR7-NU-Pad2)") (class "Default")
      (node (ref "TR7") (pin "2") (pinfunction "NU_2") (pintype "passive+no_connect"))
    )
  )
)
